# IsolationBarriers.net
KiCad netlist of a schematic drawn in Altium Designer
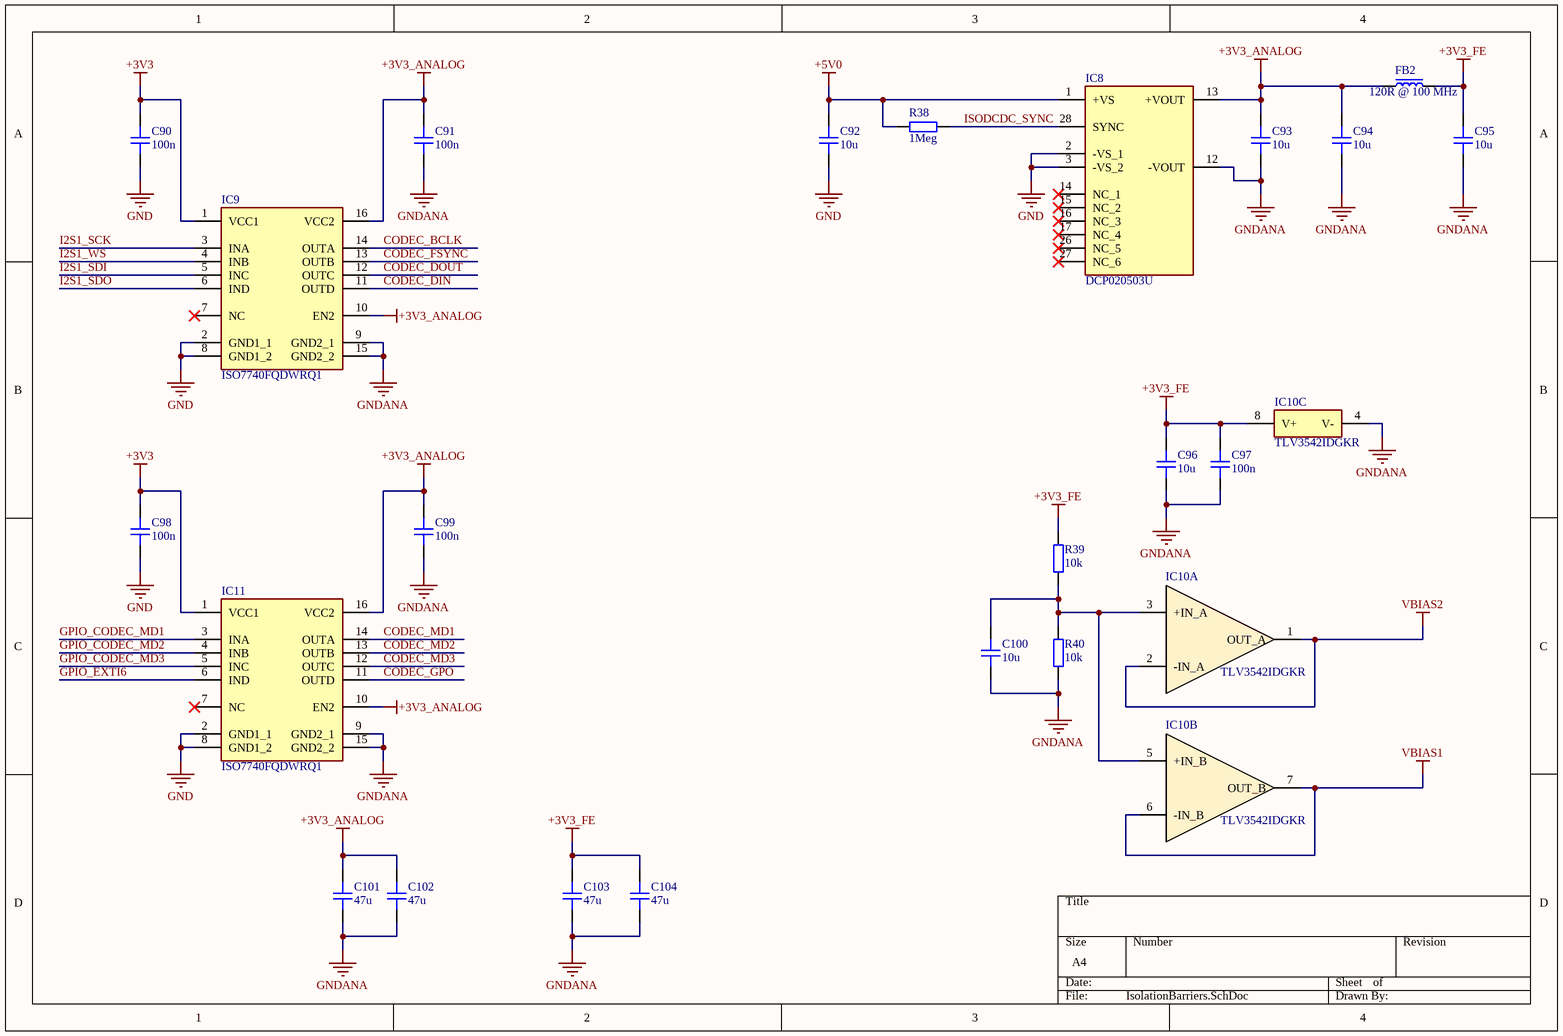
[diagram p0: IsolationBarriers.SchDoc]

(export (version "E")
  (design (tool "Eeschema 10.0.6"))
  (components
    (comp (ref "C90")
      (value "100n")
      (footprint "CAP_0402")
      (description "Capacitor SMD 0402")
      (libsource (lib "Schematic-Lib-PhilsLab") (part "CAP_0402"))
    )
    (comp (ref "C91")
      (value "100n")
      (footprint "CAP_0402")
      (description "Capacitor SMD 0402")
      (libsource (lib "Schematic-Lib-PhilsLab") (part "CAP_0402"))
    )
    (comp (ref "C92")
      (value "10u")
      (footprint "CAP_0603")
      (description "Capacitor SMD 0603")
      (libsource (lib "Schematic-Lib-PhilsLab") (part "CAP_0603"))
    )
    (comp (ref "C93")
      (value "10u")
      (footprint "CAP_0603")
      (description "Capacitor SMD 0603")
      (libsource (lib "Schematic-Lib-PhilsLab") (part "CAP_0603"))
    )
    (comp (ref "C94")
      (value "10u")
      (footprint "CAP_0603")
      (description "Capacitor SMD 0603")
      (libsource (lib "Schematic-Lib-PhilsLab") (part "CAP_0603"))
    )
    (comp (ref "C95")
      (value "10u")
      (footprint "CAP_0603")
      (description "Capacitor SMD 0603")
      (libsource (lib "Schematic-Lib-PhilsLab") (part "CAP_0603"))
    )
    (comp (ref "C96")
      (value "10u")
      (footprint "CAP_0603")
      (description "Capacitor SMD 0603")
      (libsource (lib "Schematic-Lib-PhilsLab") (part "CAP_0603"))
    )
    (comp (ref "C97")
      (value "100n")
      (footprint "CAP_0402")
      (description "Capacitor SMD 0402")
      (libsource (lib "Schematic-Lib-PhilsLab") (part "CAP_0402"))
    )
    (comp (ref "C98")
      (value "100n")
      (footprint "CAP_0402")
      (description "Capacitor SMD 0402")
      (libsource (lib "Schematic-Lib-PhilsLab") (part "CAP_0402"))
    )
    (comp (ref "C99")
      (value "100n")
      (footprint "CAP_0402")
      (description "Capacitor SMD 0402")
      (libsource (lib "Schematic-Lib-PhilsLab") (part "CAP_0402"))
    )
    (comp (ref "C100")
      (value "10u")
      (footprint "CAP_0603")
      (description "Capacitor SMD 0603")
      (libsource (lib "Schematic-Lib-PhilsLab") (part "CAP_0603"))
    )
    (comp (ref "C101")
      (value "47u")
      (footprint "CAP_1210")
      (description "Capacitor SMD 1210")
      (libsource (lib "Schematic-Lib-PhilsLab") (part "CAP_1210"))
    )
    (comp (ref "C102")
      (value "47u")
      (footprint "CAP_1210")
      (description "Capacitor SMD 1210")
      (libsource (lib "Schematic-Lib-PhilsLab") (part "CAP_1210"))
    )
    (comp (ref "C103")
      (value "47u")
      (footprint "CAP_1210")
      (description "Capacitor SMD 1210")
      (libsource (lib "Schematic-Lib-PhilsLab") (part "CAP_1210"))
    )
    (comp (ref "C104")
      (value "47u")
      (footprint "CAP_1210")
      (description "Capacitor SMD 1210")
      (libsource (lib "Schematic-Lib-PhilsLab") (part "CAP_1210"))
    )
    (comp (ref "FB2")
      (value "120R @ 100 MHz")
      (footprint "FB_0603")
      (description "Ferrite Bead SMD 0603")
      (libsource (lib "Schematic-Lib-PhilsLab") (part "FB_0603"))
    )
    (comp (ref "IC8")
      (value "DCP020503U")
      (footprint "Footprint-Lib-PhilsLab:DVB0012A")
      (description "TI Isolated DC DC Converter")
      (fields (field (name "MOUSER PART NUMBER") "595-DCP020503U"))
      (libsource (lib "Schematic-Lib-PhilsLab") (part "DCP020503U"))
    )
    (comp (ref "IC9")
      (value "ISO7740FQDWRQ1")
      (footprint "Footprint-Lib-PhilsLab:SOIC127P1030X265-16N")
      (description "Integrated Circuit")
      (fields (field (name "MOUSER PART NUMBER") "595-ISO7740FQDWRQ1"))
      (libsource (lib "Schematic-Lib-PhilsLab") (part "ISO7740FQDWRQ1"))
    )
    (comp (ref "IC10")
      (value "TLV3542IDGKR")
      (footprint "Footprint-Lib-PhilsLab:SOP65P490X110-8N")
      (description "Integrated Circuit")
      (fields (field (name "MOUSER PART NUMBER") "595-TLV3542IDGKR"))
      (libsource (lib "Schematic-Lib-PhilsLab") (part "TLV3542IDGKR"))
    )
    (comp (ref "IC11")
      (value "ISO7740FQDWRQ1")
      (footprint "Footprint-Lib-PhilsLab:SOIC127P1030X265-16N")
      (description "Integrated Circuit")
      (fields (field (name "MOUSER PART NUMBER") "595-ISO7740FQDWRQ1"))
      (libsource (lib "Schematic-Lib-PhilsLab") (part "ISO7740FQDWRQ1"))
    )
    (comp (ref "R38")
      (value "1Meg")
      (footprint "RES_0402")
      (description "Resistor SMD 0402")
      (libsource (lib "Schematic-Lib-PhilsLab") (part "RES_0402"))
    )
    (comp (ref "R39")
      (value "10k")
      (footprint "RES_0603")
      (description "Resistor SMD 0603")
      (libsource (lib "Schematic-Lib-PhilsLab") (part "RES_0603"))
    )
    (comp (ref "R40")
      (value "10k")
      (footprint "RES_0603")
      (description "Resistor SMD 0603")
      (libsource (lib "Schematic-Lib-PhilsLab") (part "RES_0603"))
    )
  )
  (nets
    (net (code "1") (name "+3V3") (class "Default")
      (node (ref "C90") (pin "2") (pinfunction "2_2") (pintype "passive"))
      (node (ref "C98") (pin "2") (pinfunction "2_2") (pintype "passive"))
      (node (ref "IC11") (pin "1") (pinfunction "VCC1_1") (pintype "passive"))
      (node (ref "IC9") (pin "1") (pinfunction "VCC1_1") (pintype "passive"))
    )
    (net (code "2") (name "+3V3_ANALOG") (class "Default")
      (node (ref "C101") (pin "2") (pinfunction "2_2") (pintype "passive"))
      (node (ref "C102") (pin "2") (pinfunction "2_2") (pintype "passive"))
      (node (ref "C91") (pin "2") (pinfunction "2_2") (pintype "passive"))
      (node (ref "C93") (pin "2") (pinfunction "2_2") (pintype "passive"))
      (node (ref "C94") (pin "2") (pinfunction "2_2") (pintype "passive"))
      (node (ref "C99") (pin "2") (pinfunction "2_2") (pintype "passive"))
      (node (ref "FB2") (pin "1") (pinfunction "1_1") (pintype "passive"))
      (node (ref "IC11") (pin "10") (pinfunction "EN2_10") (pintype "passive"))
      (node (ref "IC11") (pin "16") (pinfunction "VCC2_16") (pintype "passive"))
      (node (ref "IC8") (pin "13") (pinfunction "+VOUT_13") (pintype "passive"))
      (node (ref "IC9") (pin "10") (pinfunction "EN2_10") (pintype "passive"))
      (node (ref "IC9") (pin "16") (pinfunction "VCC2_16") (pintype "passive"))
    )
    (net (code "3") (name "+3V3_FE") (class "Default")
      (node (ref "C103") (pin "2") (pinfunction "2_2") (pintype "passive"))
      (node (ref "C104") (pin "2") (pinfunction "2_2") (pintype "passive"))
      (node (ref "C95") (pin "2") (pinfunction "2_2") (pintype "passive"))
      (node (ref "C96") (pin "2") (pinfunction "2_2") (pintype "passive"))
      (node (ref "C97") (pin "2") (pinfunction "2_2") (pintype "passive"))
      (node (ref "FB2") (pin "2") (pinfunction "2_2") (pintype "passive"))
      (node (ref "IC10") (pin "8") (pinfunction "V+_8") (pintype "passive"))
      (node (ref "R39") (pin "2") (pinfunction "2_2") (pintype "passive"))
    )
    (net (code "4") (name "+5V0") (class "Default")
      (node (ref "C92") (pin "2") (pinfunction "2_2") (pintype "passive"))
      (node (ref "IC8") (pin "1") (pinfunction "+VS_1") (pintype "passive"))
      (node (ref "R38") (pin "1") (pinfunction "1_1") (pintype "passive"))
    )
    (net (code "5") (name "/CODEC_BCLK") (class "Default")
      (node (ref "IC9") (pin "14") (pinfunction "OUTA_14") (pintype "passive"))
    )
    (net (code "6") (name "/CODEC_DIN") (class "Default")
      (node (ref "IC9") (pin "11") (pinfunction "OUTD_11") (pintype "passive"))
    )
    (net (code "7") (name "/CODEC_DOUT") (class "Default")
      (node (ref "IC9") (pin "12") (pinfunction "OUTC_12") (pintype "passive"))
    )
    (net (code "8") (name "/CODEC_FSYNC") (class "Default")
      (node (ref "IC9") (pin "13") (pinfunction "OUTB_13") (pintype "passive"))
    )
    (net (code "9") (name "/CODEC_GPO") (class "Default")
      (node (ref "IC11") (pin "11") (pinfunction "OUTD_11") (pintype "passive"))
    )
    (net (code "10") (name "/CODEC_MD1") (class "Default")
      (node (ref "IC11") (pin "14") (pinfunction "OUTA_14") (pintype "passive"))
    )
    (net (code "11") (name "/CODEC_MD2") (class "Default")
      (node (ref "IC11") (pin "13") (pinfunction "OUTB_13") (pintype "passive"))
    )
    (net (code "12") (name "/CODEC_MD3") (class "Default")
      (node (ref "IC11") (pin "12") (pinfunction "OUTC_12") (pintype "passive"))
    )
    (net (code "13") (name "/GPIO_CODEC_MD1") (class "Default")
      (node (ref "IC11") (pin "3") (pinfunction "INA_3") (pintype "passive"))
    )
    (net (code "14") (name "/GPIO_CODEC_MD2") (class "Default")
      (node (ref "IC11") (pin "4") (pinfunction "INB_4") (pintype "passive"))
    )
    (net (code "15") (name "/GPIO_CODEC_MD3") (class "Default")
      (node (ref "IC11") (pin "5") (pinfunction "INC_5") (pintype "passive"))
    )
    (net (code "16") (name "/GPIO_EXTI6") (class "Default")
      (node (ref "IC11") (pin "6") (pinfunction "IND_6") (pintype "passive"))
    )
    (net (code "17") (name "/I2S1_SCK") (class "Default")
      (node (ref "IC9") (pin "3") (pinfunction "INA_3") (pintype "passive"))
    )
    (net (code "18") (name "/I2S1_SDI") (class "Default")
      (node (ref "IC9") (pin "5") (pinfunction "INC_5") (pintype "passive"))
    )
    (net (code "19") (name "/I2S1_SDO") (class "Default")
      (node (ref "IC9") (pin "6") (pinfunction "IND_6") (pintype "passive"))
    )
    (net (code "20") (name "/I2S1_WS") (class "Default")
      (node (ref "IC9") (pin "4") (pinfunction "INB_4") (pintype "passive"))
    )
    (net (code "21") (name "/ISODCDC_SYNC") (class "Default")
      (node (ref "IC8") (pin "28") (pinfunction "SYNC_28") (pintype "passive"))
      (node (ref "R38") (pin "2") (pinfunction "2_2") (pintype "passive"))
    )
    (net (code "22") (name "GND") (class "Default")
      (node (ref "C90") (pin "1") (pinfunction "1_1") (pintype "passive"))
      (node (ref "C92") (pin "1") (pinfunction "1_1") (pintype "passive"))
      (node (ref "C98") (pin "1") (pinfunction "1_1") (pintype "passive"))
      (node (ref "IC11") (pin "2") (pinfunction "GND1_1_2") (pintype "passive"))
      (node (ref "IC11") (pin "8") (pinfunction "GND1_2_8") (pintype "passive"))
      (node (ref "IC8") (pin "2") (pinfunction "-VS_1_2") (pintype "passive"))
      (node (ref "IC8") (pin "3") (pinfunction "-VS_2_3") (pintype "passive"))
      (node (ref "IC9") (pin "2") (pinfunction "GND1_1_2") (pintype "passive"))
      (node (ref "IC9") (pin "8") (pinfunction "GND1_2_8") (pintype "passive"))
    )
    (net (code "23") (name "GNDANA") (class "Default")
      (node (ref "C100") (pin "1") (pinfunction "1_1") (pintype "passive"))
      (node (ref "C101") (pin "1") (pinfunction "1_1") (pintype "passive"))
      (node (ref "C102") (pin "1") (pinfunction "1_1") (pintype "passive"))
      (node (ref "C103") (pin "1") (pinfunction "1_1") (pintype "passive"))
      (node (ref "C104") (pin "1") (pinfunction "1_1") (pintype "passive"))
      (node (ref "C91") (pin "1") (pinfunction "1_1") (pintype "passive"))
      (node (ref "C93") (pin "1") (pinfunction "1_1") (pintype "passive"))
      (node (ref "C94") (pin "1") (pinfunction "1_1") (pintype "passive"))
      (node (ref "C95") (pin "1") (pinfunction "1_1") (pintype "passive"))
      (node (ref "C96") (pin "1") (pinfunction "1_1") (pintype "passive"))
      (node (ref "C97") (pin "1") (pinfunction "1_1") (pintype "passive"))
      (node (ref "C99") (pin "1") (pinfunction "1_1") (pintype "passive"))
      (node (ref "IC10") (pin "4") (pinfunction "V-_4") (pintype "passive"))
      (node (ref "IC11") (pin "15") (pinfunction "GND2_2_15") (pintype "passive"))
      (node (ref "IC11") (pin "9") (pinfunction "GND2_1_9") (pintype "passive"))
      (node (ref "IC8") (pin "12") (pinfunction "-VOUT_12") (pintype "passive"))
      (node (ref "IC9") (pin "15") (pinfunction "GND2_2_15") (pintype "passive"))
      (node (ref "IC9") (pin "9") (pinfunction "GND2_1_9") (pintype "passive"))
      (node (ref "R40") (pin "1") (pinfunction "1_1") (pintype "passive"))
    )
    (net (code "24") (name "Net-(IC10A-+IN_A)") (class "Default")
      (node (ref "C100") (pin "2") (pinfunction "2_2") (pintype "passive"))
      (node (ref "IC10") (pin "3") (pinfunction "+IN_A_3") (pintype "passive"))
      (node (ref "IC10") (pin "5") (pinfunction "+IN_B_5") (pintype "passive"))
      (node (ref "R39") (pin "1") (pinfunction "1_1") (pintype "passive"))
      (node (ref "R40") (pin "2") (pinfunction "2_2") (pintype "passive"))
    )
    (net (code "25") (name "VBIAS1") (class "Default")
      (node (ref "IC10") (pin "6") (pinfunction "-IN_B_6") (pintype "passive"))
      (node (ref "IC10") (pin "7") (pinfunction "OUT_B_7") (pintype "passive"))
    )
    (net (code "26") (name "VBIAS2") (class "Default")
      (node (ref "IC10") (pin "1") (pinfunction "OUT_A_1") (pintype "passive"))
      (node (ref "IC10") (pin "2") (pinfunction "-IN_A_2") (pintype "passive"))
    )
    (net (code "27") (name "unconnected-(IC8-NC_1-Pad14)") (class "Default")
      (node (ref "IC8") (pin "14") (pinfunction "NC_1_14") (pintype "passive+no_connect"))
    )
    (net (code "28") (name "unconnected-(IC8-NC_2-Pad15)") (class "Default")
      (node (ref "IC8") (pin "15") (pinfunction "NC_2_15") (pintype "passive+no_connect"))
    )
    (net (code "29") (name "unconnected-(IC8-NC_3-Pad16)") (class "Default")
      (node (ref "IC8") (pin "16") (pinfunction "NC_3_16") (pintype "passive+no_connect"))
    )
    (net (code "30") (name "unconnected-(IC8-NC_4-Pad17)") (class "Default")
      (node (ref "IC8") (pin "17") (pinfunction "NC_4_17") (pintype "passive+no_connect"))
    )
    (net (code "31") (name "unconnected-(IC8-NC_5-Pad26)") (class "Default")
      (node (ref "IC8") (pin "26") (pinfunction "NC_5_26") (pintype "passive+no_connect"))
    )
    (net (code "32") (name "unconnected-(IC8-NC_6-Pad27)") (class "Default")
      (node (ref "IC8") (pin "27") (pinfunction "NC_6_27") (pintype "passive+no_connect"))
    )
    (net (code "33") (name "unconnected-(IC9-NC-Pad7)") (class "Default")
      (node (ref "IC9") (pin "7") (pinfunction "NC_7") (pintype "passive+no_connect"))
    )
    (net (code "34") (name "unconnected-(IC11-NC-Pad7)") (class "Default")
      (node (ref "IC11") (pin "7") (pinfunction "NC_7") (pintype "passive+no_connect"))
    )
  )
)
